# ROS-Robot-Controller.net
KiCad netlist of a schematic drawn in Altium Designer
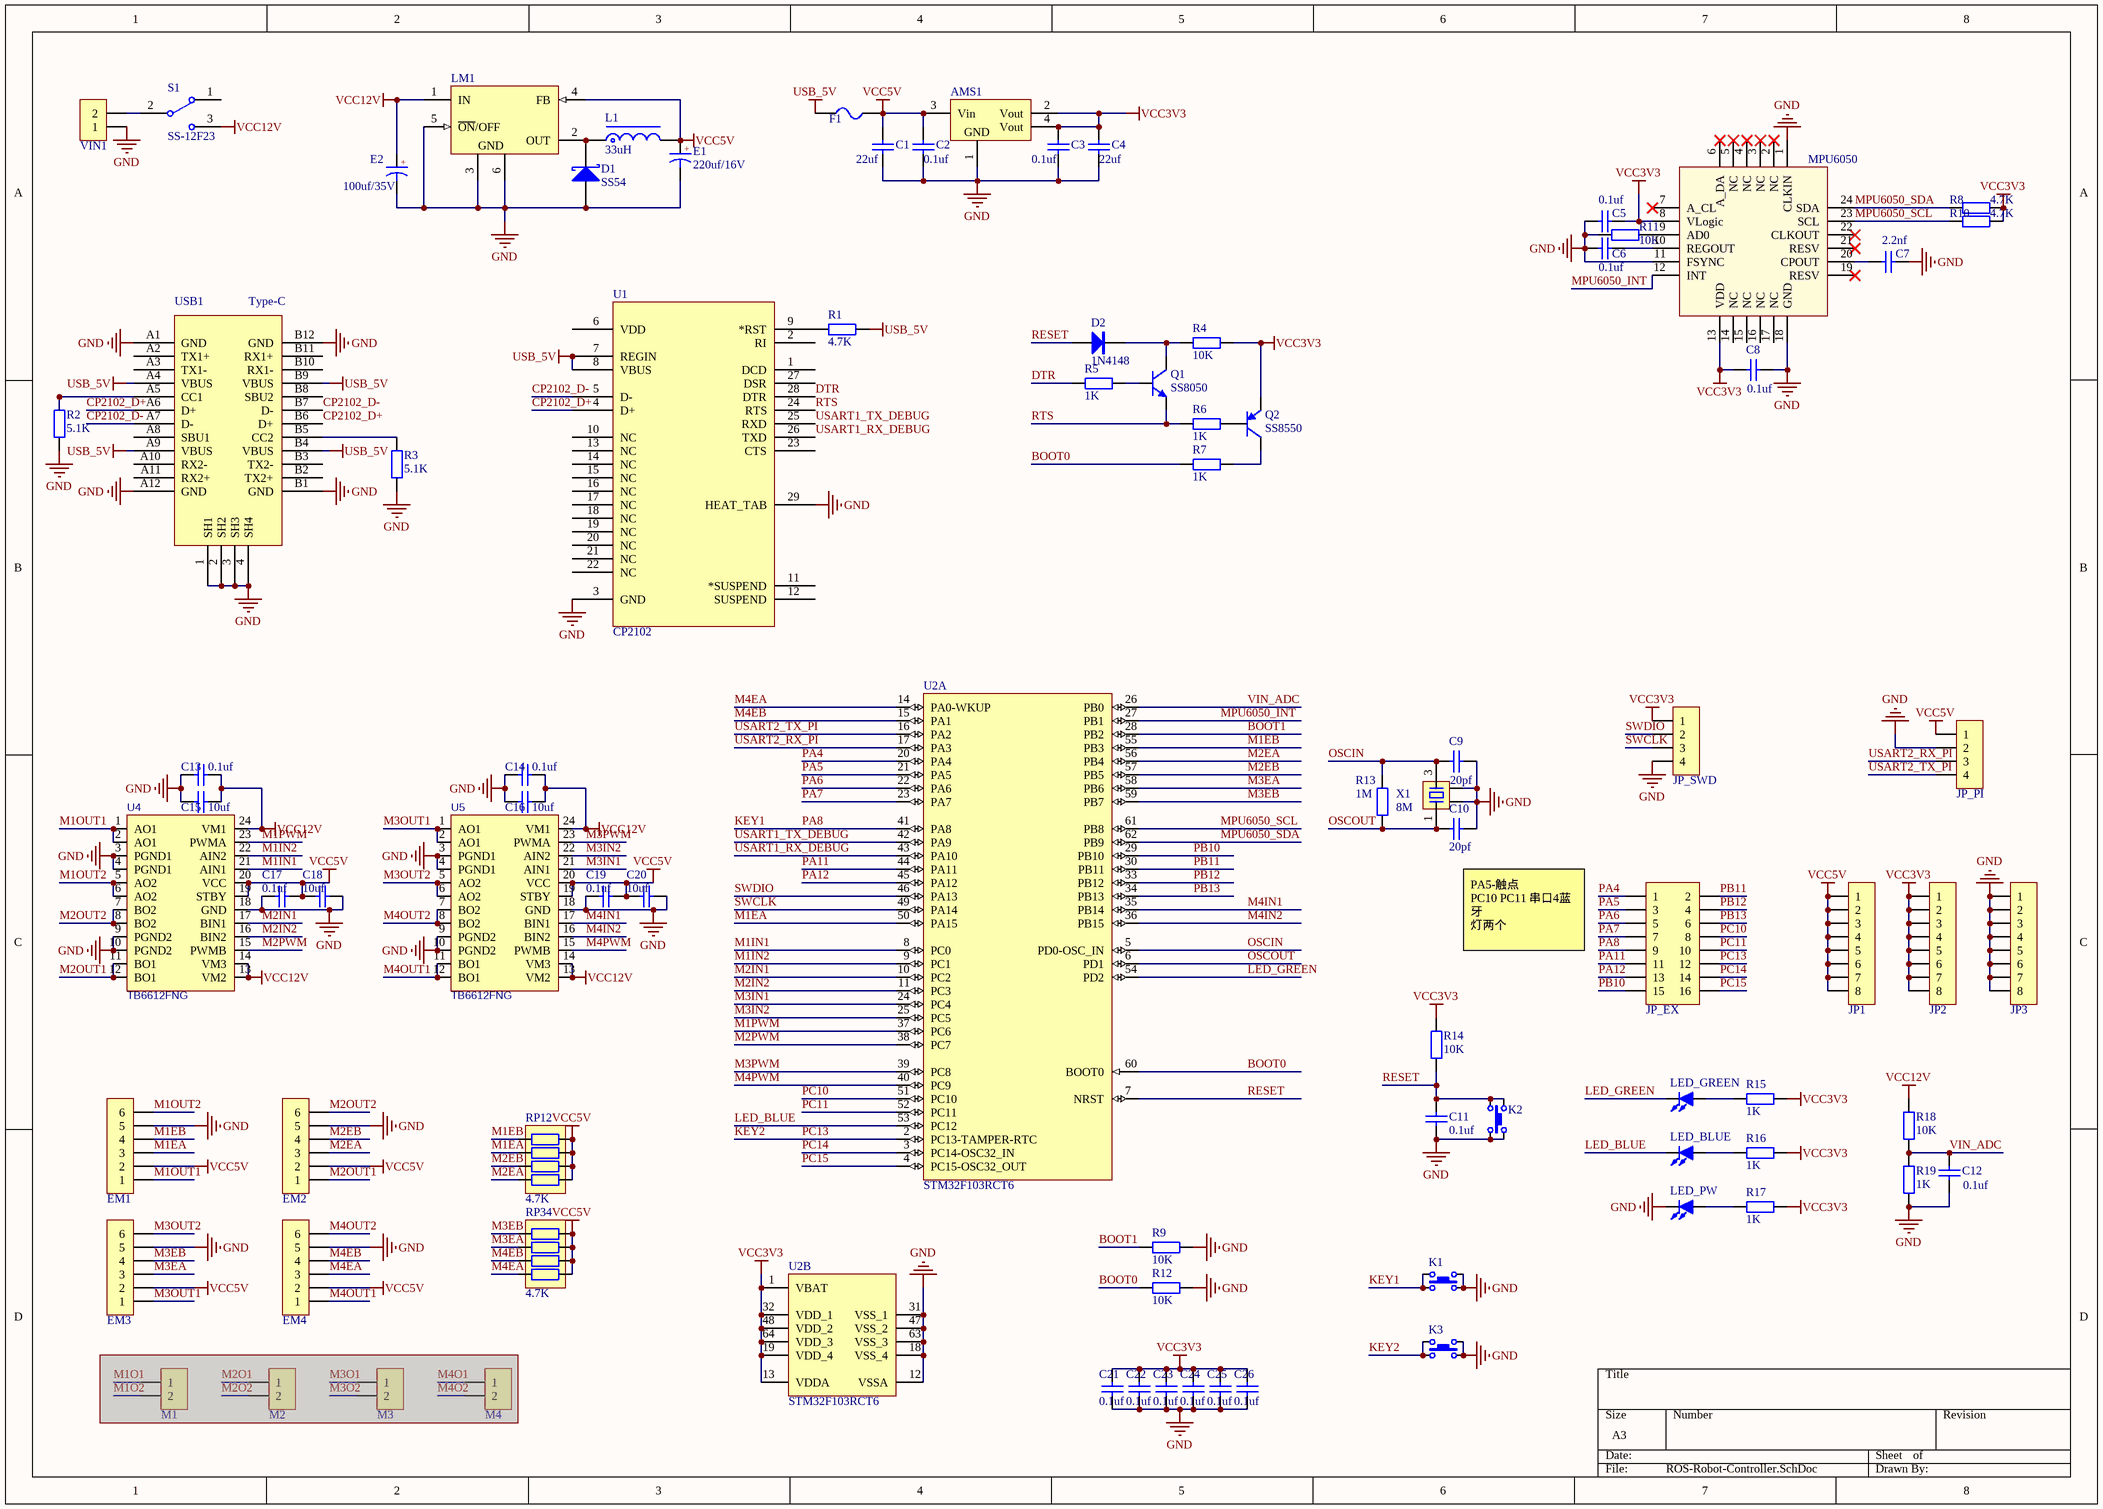
[diagram p0: ROS-Robot-Controller.SchDoc]

(export (version "E")
  (design (tool "Eeschema 10.0.6"))
  (components
    (comp (ref "AMS1")
      (value "AMS1117-3V3")
      (footprint "SOT223_L")
      (description "三端稳压芯片")
      (libsource (lib "1.1 - 电源类芯片") (part "AMS1117"))
    )
    (comp (ref "C1")
      (value "22uf")
      (footprint "C0402_L")
      (description "贴片电容")
      (libsource (lib "0.1 - 电阻-电容-电感-电位器") (part "C"))
    )
    (comp (ref "C2")
      (value "0.1uf")
      (footprint "C0402_L")
      (description "贴片电容")
      (libsource (lib "0.1 - 电阻-电容-电感-电位器") (part "C"))
    )
    (comp (ref "C3")
      (value "0.1uf")
      (footprint "C0402_L")
      (description "贴片电容")
      (libsource (lib "0.1 - 电阻-电容-电感-电位器") (part "C"))
    )
    (comp (ref "C4")
      (value "22uf")
      (footprint "C0402_L")
      (description "贴片电容")
      (libsource (lib "0.1 - 电阻-电容-电感-电位器") (part "C"))
    )
    (comp (ref "C5")
      (value "0.1uf")
      (footprint "C0402_L")
      (description "贴片电容")
      (libsource (lib "0.1 - 电阻-电容-电感-电位器") (part "C"))
    )
    (comp (ref "C6")
      (value "0.1uf")
      (footprint "C0402_L")
      (description "贴片电容")
      (libsource (lib "0.1 - 电阻-电容-电感-电位器") (part "C"))
    )
    (comp (ref "C7")
      (value "2.2nf")
      (footprint "C0402_L")
      (description "贴片电容")
      (libsource (lib "0.1 - 电阻-电容-电感-电位器") (part "C"))
    )
    (comp (ref "C8")
      (value "0.1uf")
      (footprint "C0402_L")
      (description "贴片电容")
      (libsource (lib "0.1 - 电阻-电容-电感-电位器") (part "C"))
    )
    (comp (ref "C9")
      (value "20pf")
      (footprint "C0402_L")
      (description "贴片电容")
      (libsource (lib "0.1 - 电阻-电容-电感-电位器") (part "C"))
    )
    (comp (ref "C10")
      (value "20pf")
      (footprint "C0402_L")
      (description "贴片电容")
      (libsource (lib "0.1 - 电阻-电容-电感-电位器") (part "C"))
    )
    (comp (ref "C11")
      (value "0.1uf")
      (footprint "C0402_L")
      (description "贴片电容")
      (libsource (lib "0.1 - 电阻-电容-电感-电位器") (part "C"))
    )
    (comp (ref "C12")
      (value "0.1uf")
      (footprint "C0603_L")
      (description "贴片电容")
      (libsource (lib "0.1 - 电阻-电容-电感-电位器") (part "C"))
    )
    (comp (ref "C13")
      (value "0.1uf")
      (footprint "C0603_L")
      (description "贴片电容")
      (libsource (lib "0.1 - 电阻-电容-电感-电位器") (part "C"))
    )
    (comp (ref "C14")
      (value "0.1uf")
      (footprint "C0603_L")
      (description "贴片电容")
      (libsource (lib "0.1 - 电阻-电容-电感-电位器") (part "C"))
    )
    (comp (ref "C15")
      (value "10uf")
      (footprint "C0603_L")
      (description "贴片电容")
      (libsource (lib "0.1 - 电阻-电容-电感-电位器") (part "C"))
    )
    (comp (ref "C16")
      (value "10uf")
      (footprint "C0603_L")
      (description "贴片电容")
      (libsource (lib "0.1 - 电阻-电容-电感-电位器") (part "C"))
    )
    (comp (ref "C17")
      (value "0.1uf")
      (footprint "C0402_L")
      (description "贴片电容")
      (libsource (lib "0.1 - 电阻-电容-电感-电位器") (part "C"))
    )
    (comp (ref "C18")
      (value "10uf")
      (footprint "C0402_L")
      (description "贴片电容")
      (libsource (lib "0.1 - 电阻-电容-电感-电位器") (part "C"))
    )
    (comp (ref "C19")
      (value "0.1uf")
      (footprint "C0402_L")
      (description "贴片电容")
      (libsource (lib "0.1 - 电阻-电容-电感-电位器") (part "C"))
    )
    (comp (ref "C20")
      (value "10uf")
      (footprint "C0402_L")
      (description "贴片电容")
      (libsource (lib "0.1 - 电阻-电容-电感-电位器") (part "C"))
    )
    (comp (ref "C21")
      (value "0.1uf")
      (footprint "C0402_L")
      (description "贴片电容")
      (libsource (lib "0.1 - 电阻-电容-电感-电位器") (part "C"))
    )
    (comp (ref "C22")
      (value "0.1uf")
      (footprint "C0402_L")
      (description "贴片电容")
      (libsource (lib "0.1 - 电阻-电容-电感-电位器") (part "C"))
    )
    (comp (ref "C23")
      (value "0.1uf")
      (footprint "C0402_L")
      (description "贴片电容")
      (libsource (lib "0.1 - 电阻-电容-电感-电位器") (part "C"))
    )
    (comp (ref "C24")
      (value "0.1uf")
      (footprint "C0402_L")
      (description "贴片电容")
      (libsource (lib "0.1 - 电阻-电容-电感-电位器") (part "C"))
    )
    (comp (ref "C25")
      (value "0.1uf")
      (footprint "C0402_L")
      (description "贴片电容")
      (libsource (lib "0.1 - 电阻-电容-电感-电位器") (part "C"))
    )
    (comp (ref "C26")
      (value "0.1uf")
      (footprint "C0402_L")
      (description "贴片电容")
      (libsource (lib "0.1 - 电阻-电容-电感-电位器") (part "C"))
    )
    (comp (ref "D1")
      (value "SS54")
      (footprint "SMA")
      (description "肖特基二极管(5A/40V)")
      (libsource (lib "0.2 - 二极管-TVS-整流桥") (part "SS14"))
    )
    (comp (ref "D2")
      (value "1N4148")
      (footprint "SOD-323")
      (description "开关二极管")
      (libsource (lib "0.2 - 二极管-TVS-整流桥") (part "1N4148"))
    )
    (comp (ref "E1")
      (value "220uf/16V")
      (footprint "CE D(6.3*7.7)")
      (description "贴片电解电容")
      (libsource (lib "0.1 - 电阻-电容-电感-电位器") (part "CE_SMD"))
    )
    (comp (ref "E2")
      (value "100uf/35V")
      (footprint "CE D(6.3*7.7)")
      (description "贴片电解电容")
      (libsource (lib "0.1 - 电阻-电容-电感-电位器") (part "CE_SMD"))
    )
    (comp (ref "EM1")
      (value "HDR-1X6")
      (footprint "XH2.54-LI-6P")
      (description "6P接插件")
      (libsource (lib "5.4 - 接插件-脚距2.54 (100mil) ") (part "Header 6"))
    )
    (comp (ref "EM2")
      (value "HDR-1X6")
      (footprint "XH2.54-LI-6P")
      (description "6P接插件")
      (libsource (lib "5.4 - 接插件-脚距2.54 (100mil) ") (part "Header 6"))
    )
    (comp (ref "EM3")
      (value "HDR-1X6")
      (footprint "XH2.54-LI-6P")
      (description "6P接插件")
      (libsource (lib "5.4 - 接插件-脚距2.54 (100mil) ") (part "Header 6"))
    )
    (comp (ref "EM4")
      (value "HDR-1X6")
      (footprint "XH2.54-LI-6P")
      (description "6P接插件")
      (libsource (lib "5.4 - 接插件-脚距2.54 (100mil) ") (part "Header 6"))
    )
    (comp (ref "F1")
      (value "MSMD200-8V 2A")
      (footprint "FU 0603")
      (description "贴片保险丝")
      (libsource (lib "0.5 - 保险丝-晶振-光耦") (part "FU"))
    )
    (comp (ref "JP1")
      (value "HDR-1X8")
      (footprint "HDR2.54-LI-8P")
      (description "8P接插件")
      (libsource (lib "5.4 - 接插件-脚距2.54 (100mil) ") (part "Header 8"))
    )
    (comp (ref "JP2")
      (value "HDR-1X8")
      (footprint "HDR2.54-LI-8P")
      (description "8P接插件")
      (libsource (lib "5.4 - 接插件-脚距2.54 (100mil) ") (part "Header 8"))
    )
    (comp (ref "JP3")
      (value "HDR-1X8")
      (footprint "HDR2.54-LI-8P")
      (description "8P接插件")
      (libsource (lib "5.4 - 接插件-脚距2.54 (100mil) ") (part "Header 8"))
    )
    (comp (ref "JP_EX")
      (value "Header 8X2")
      (footprint "HDR2.54-LI-2x8P")
      (description "8*2P接插件")
      (libsource (lib "5.4 - 接插件-脚距2.54 (100mil) ") (part "Header 8X2"))
    )
    (comp (ref "JP_PI")
      (value "HDR-1X4")
      (footprint "HDR2.54-LI-4P")
      (description "4P接插件")
      (libsource (lib "5.4 - 接插件-脚距2.54 (100mil) ") (part "Header 4"))
    )
    (comp (ref "JP_SWD")
      (value "HDR-1X4")
      (footprint "XH2.54-WI-4P")
      (description "4P接插件")
      (libsource (lib "5.4 - 接插件-脚距2.54 (100mil) ") (part "Header 4"))
    )
    (comp (ref "K1")
      (value "TACT 4P")
      (footprint "SW-SMD_4P-L4.2-W3.3-P2.15-LS5.1")
      (description "Button")
      (libsource (lib "KitSprout") (part "ButtonTACT"))
    )
    (comp (ref "K2")
      (value "TACT 4P")
      (footprint "SW-SMD_4P-L4.2-W3.3-P2.15-LS5.1")
      (description "Button")
      (libsource (lib "KitSprout") (part "ButtonTACT"))
    )
    (comp (ref "K3")
      (value "TACT 4P")
      (footprint "SW-SMD_4P-L4.2-W3.3-P2.15-LS5.1")
      (description "Button")
      (libsource (lib "KitSprout") (part "ButtonTACT"))
    )
    (comp (ref "L1")
      (value "33uH")
      (footprint "CDRH74")
      (description "CDRH功率屏蔽电感")
      (libsource (lib "0.1 - 电阻-电容-电感-电位器") (part "L-CDRH"))
    )
    (comp (ref "LED_BLUE")
      (value "红色")
      (footprint "LED_0402_RED")
      (description "贴片LED")
      (libsource (lib "0.3 - LED发光二极管") (part "LED-SMD"))
    )
    (comp (ref "LED_GREEN")
      (value "红色")
      (footprint "LED_0402_RED")
      (description "贴片LED")
      (libsource (lib "0.3 - LED发光二极管") (part "LED-SMD"))
    )
    (comp (ref "LED_PW")
      (value "红色")
      (footprint "LED_0402_RED")
      (description "贴片LED")
      (libsource (lib "0.3 - LED发光二极管") (part "LED-SMD"))
    )
    (comp (ref "LM1")
      (value "LM2596S")
      (footprint "TO263-5A")
      (description "3A DC-DC降压芯片")
      (libsource (lib "1.1 - 电源类芯片") (part "LM2596S"))
    )
    (comp (ref "M1")
      (value "HDR-1X2")
      (footprint "KF350-2P")
      (description "2P接插件")
      (libsource (lib "5.5 - 接插件-脚距3.5") (part "Header 2"))
    )
    (comp (ref "M2")
      (value "HDR-1X2")
      (footprint "KF350-2P")
      (description "2P接插件")
      (libsource (lib "5.5 - 接插件-脚距3.5") (part "Header 2"))
    )
    (comp (ref "M3")
      (value "HDR-1X2")
      (footprint "KF350-2P")
      (description "2P接插件")
      (libsource (lib "5.5 - 接插件-脚距3.5") (part "Header 2"))
    )
    (comp (ref "M4")
      (value "HDR-1X2")
      (footprint "KF350-2P")
      (description "2P接插件")
      (libsource (lib "5.5 - 接插件-脚距3.5") (part "Header 2"))
    )
    (comp (ref "Q1")
      (value "SS8050")
      (footprint "SOT23-3N")
      (description "高频放大-NPN型")
      (libsource (lib "0.4 - 三极管-场效应管-可控硅") (part "8050-SMD"))
    )
    (comp (ref "Q2")
      (value "SS8550")
      (footprint "SOT23-3N")
      (description "高频放大-PNP型")
      (libsource (lib "0.4 - 三极管-场效应管-可控硅") (part "8550-SMD"))
    )
    (comp (ref "R1")
      (value "4.7K")
      (footprint "R0402_L")
      (description "贴片电阻")
      (libsource (lib "0.1 - 电阻-电容-电感-电位器") (part "R"))
    )
    (comp (ref "R2")
      (value "5.1K")
      (footprint "R0402_L")
      (description "贴片电阻")
      (libsource (lib "0.1 - 电阻-电容-电感-电位器") (part "R"))
    )
    (comp (ref "R3")
      (value "5.1K")
      (footprint "R0402_L")
      (description "贴片电阻")
      (libsource (lib "0.1 - 电阻-电容-电感-电位器") (part "R"))
    )
    (comp (ref "R4")
      (value "10K")
      (footprint "R0402_L")
      (description "贴片电阻")
      (libsource (lib "0.1 - 电阻-电容-电感-电位器") (part "R"))
    )
    (comp (ref "R5")
      (value "1K")
      (footprint "R0402_L")
      (description "贴片电阻")
      (libsource (lib "0.1 - 电阻-电容-电感-电位器") (part "R"))
    )
    (comp (ref "R6")
      (value "1K")
      (footprint "R0402_L")
      (description "贴片电阻")
      (libsource (lib "0.1 - 电阻-电容-电感-电位器") (part "R"))
    )
    (comp (ref "R7")
      (value "1K")
      (footprint "R0402_L")
      (description "贴片电阻")
      (libsource (lib "0.1 - 电阻-电容-电感-电位器") (part "R"))
    )
    (comp (ref "R8")
      (value "4.7K")
      (footprint "R0402_L")
      (description "贴片电阻")
      (libsource (lib "0.1 - 电阻-电容-电感-电位器") (part "R"))
    )
    (comp (ref "R9")
      (value "10K")
      (footprint "R0402_L")
      (description "贴片电阻")
      (libsource (lib "0.1 - 电阻-电容-电感-电位器") (part "R"))
    )
    (comp (ref "R10")
      (value "4.7K")
      (footprint "R0402_L")
      (description "贴片电阻")
      (libsource (lib "0.1 - 电阻-电容-电感-电位器") (part "R"))
    )
    (comp (ref "R11")
      (value "10K")
      (footprint "R0402_L")
      (description "贴片电阻")
      (libsource (lib "0.1 - 电阻-电容-电感-电位器") (part "R"))
    )
    (comp (ref "R12")
      (value "10K")
      (footprint "R0402_L")
      (description "贴片电阻")
      (libsource (lib "0.1 - 电阻-电容-电感-电位器") (part "R"))
    )
    (comp (ref "R13")
      (value "1M")
      (footprint "R0402_L")
      (description "贴片电阻")
      (libsource (lib "0.1 - 电阻-电容-电感-电位器") (part "R"))
    )
    (comp (ref "R14")
      (value "10K")
      (footprint "R0402_L")
      (description "贴片电阻")
      (libsource (lib "0.1 - 电阻-电容-电感-电位器") (part "R"))
    )
    (comp (ref "R15")
      (value "1K")
      (footprint "R0402_L")
      (description "贴片电阻")
      (libsource (lib "0.1 - 电阻-电容-电感-电位器") (part "R"))
    )
    (comp (ref "R16")
      (value "1K")
      (footprint "R0402_L")
      (description "贴片电阻")
      (libsource (lib "0.1 - 电阻-电容-电感-电位器") (part "R"))
    )
    (comp (ref "R17")
      (value "1K")
      (footprint "R0402_L")
      (description "贴片电阻")
      (libsource (lib "0.1 - 电阻-电容-电感-电位器") (part "R"))
    )
    (comp (ref "R18")
      (value "10K")
      (footprint "R0603_L")
      (description "贴片电阻")
      (libsource (lib "0.1 - 电阻-电容-电感-电位器") (part "R"))
    )
    (comp (ref "R19")
      (value "1K")
      (footprint "R0603_L")
      (description "贴片电阻")
      (libsource (lib "0.1 - 电阻-电容-电感-电位器") (part "R"))
    )
    (comp (ref "RP12")
      (value "4.7K")
      (footprint "RCA-8P4R-0402")
      (description "贴片4P排阻")
      (libsource (lib "0.1 - 电阻-电容-电感-电位器") (part "R-8P4R"))
    )
    (comp (ref "RP34")
      (value "4.7K")
      (footprint "RCA-8P4R-0402")
      (description "贴片4P排阻")
      (libsource (lib "0.1 - 电阻-电容-电感-电位器") (part "R-8P4R"))
    )
    (comp (ref "S1")
      (value "SS-12F23")
      (footprint "SS-12D10")
      (description "1路波动开关")
      (libsource (lib "0.7 - 常用按键-开关-蜂鸣器-电池-测试点") (part "SSW-1P"))
    )
    (comp (ref "U1")
      (value "CP2102")
      (footprint "QFN-28")
      (description "USB转TTL")
      (libsource (lib "mLib") (part "CP2102"))
    )
    (comp (ref "U2")
      (value "STM32F103RCT6")
      (footprint "LQFP64_N")
      (libsource (lib "2.4 - STM32 F1系列单片机") (part "STM32F103RCT6"))
    )
    (comp (ref "U3")
      (value "MPU6050")
      (footprint "QFN-24")
      (description "六轴传感器")
      (libsource (lib "mLib") (part "MPU6050"))
    )
    (comp (ref "U4")
      (value "TB6612FNG")
      (footprint "SSOP24_M")
      (description "电机驱动")
      (libsource (lib "1.0 - 常见芯片") (part "TB6612FNG"))
    )
    (comp (ref "U5")
      (value "TB6612FNG")
      (footprint "SSOP24_M")
      (description "电机驱动")
      (libsource (lib "1.0 - 常见芯片") (part "TB6612FNG"))
    )
    (comp (ref "USB1")
      (value "Type-C")
      (footprint "Type-C-TOP")
      (libsource (lib "MyPcbLib") (part "USB-Type-C-TOP"))
    )
    (comp (ref "VIN1")
      (value "HDR-1X2")
      (footprint "KF301-5.0-2P")
      (description "2P接插件")
      (libsource (lib "6.0 - 接插件-脚距5.0") (part "Header 2"))
    )
    (comp (ref "X1")
      (value "8M")
      (footprint "OSC 3225-4P")
      (description "4脚无源晶振")
      (libsource (lib "0.5 - 保险丝-晶振-光耦") (part "XTAL-4P"))
    )
  )
  (nets
    (net (code "1") (name "/BOOT0") (class "Default")
      (node (ref "R12") (pin "1") (pinfunction "1_1") (pintype "passive"))
      (node (ref "R7") (pin "2") (pinfunction "2_2") (pintype "passive"))
      (node (ref "U2") (pin "60") (pinfunction "BOOT0_60") (pintype "input"))
    )
    (net (code "2") (name "/BOOT1") (class "Default")
      (node (ref "R9") (pin "1") (pinfunction "1_1") (pintype "passive"))
      (node (ref "U2") (pin "28") (pinfunction "PB2_28") (pintype "bidirectional"))
    )
    (net (code "3") (name "/CP2102_D+") (class "Default")
      (node (ref "U1") (pin "4") (pinfunction "D+_4") (pintype "passive"))
      (node (ref "USB1") (pin "A6") (pinfunction "D+_A6") (pintype "passive"))
      (node (ref "USB1") (pin "B6") (pinfunction "D+_B6") (pintype "passive"))
    )
    (net (code "4") (name "/CP2102_D-") (class "Default")
      (node (ref "U1") (pin "5") (pinfunction "D-_5") (pintype "passive"))
      (node (ref "USB1") (pin "A7") (pinfunction "D-_A7") (pintype "passive"))
      (node (ref "USB1") (pin "B7") (pinfunction "D-_B7") (pintype "passive"))
    )
    (net (code "5") (name "/DTR") (class "Default")
      (node (ref "R5") (pin "1") (pinfunction "1_1") (pintype "passive"))
      (node (ref "U1") (pin "28") (pinfunction "DTR_28") (pintype "passive"))
    )
    (net (code "6") (name "/KEY1") (class "Default")
      (node (ref "JP_EX") (pin "9") (pinfunction "9_9") (pintype "passive"))
      (node (ref "K1") (pin "1") (pinfunction "1_1") (pintype "passive"))
      (node (ref "K1") (pin "3") (pinfunction "3_3") (pintype "passive"))
      (node (ref "U2") (pin "41") (pinfunction "PA8_41") (pintype "bidirectional"))
    )
    (net (code "7") (name "/KEY2") (class "Default")
      (node (ref "JP_EX") (pin "12") (pinfunction "12_12") (pintype "passive"))
      (node (ref "K3") (pin "1") (pinfunction "1_1") (pintype "passive"))
      (node (ref "K3") (pin "3") (pinfunction "3_3") (pintype "passive"))
      (node (ref "U2") (pin "2") (pinfunction "PC13-TAMPER-RTC_2") (pintype "bidirectional"))
    )
    (net (code "8") (name "/LED_BLUE") (class "Default")
      (node (ref "LED_BLUE") (pin "2") (pinfunction "K_2") (pintype "passive"))
      (node (ref "U2") (pin "53") (pinfunction "PC12_53") (pintype "bidirectional"))
    )
    (net (code "9") (name "/LED_GREEN") (class "Default")
      (node (ref "LED_GREEN") (pin "2") (pinfunction "K_2") (pintype "passive"))
      (node (ref "U2") (pin "54") (pinfunction "PD2_54") (pintype "bidirectional"))
    )
    (net (code "10") (name "/M1EA") (class "Default")
      (node (ref "EM1") (pin "3") (pinfunction "3_3") (pintype "passive"))
      (node (ref "RP12") (pin "2") (pinfunction "2_2") (pintype "passive"))
      (node (ref "U2") (pin "50") (pinfunction "PA15_50") (pintype "bidirectional"))
    )
    (net (code "11") (name "/M1EB") (class "Default")
      (node (ref "EM1") (pin "4") (pinfunction "4_4") (pintype "passive"))
      (node (ref "RP12") (pin "1") (pinfunction "1_1") (pintype "passive"))
      (node (ref "U2") (pin "55") (pinfunction "PB3_55") (pintype "bidirectional"))
    )
    (net (code "12") (name "/M1IN1") (class "Default")
      (node (ref "U2") (pin "8") (pinfunction "PC0_8") (pintype "bidirectional"))
      (node (ref "U4") (pin "21") (pinfunction "AIN1_21") (pintype "passive"))
    )
    (net (code "13") (name "/M1IN2") (class "Default")
      (node (ref "U2") (pin "9") (pinfunction "PC1_9") (pintype "bidirectional"))
      (node (ref "U4") (pin "22") (pinfunction "AIN2_22") (pintype "passive"))
    )
    (net (code "14") (name "/M1O1") (class "Default")
      (node (ref "M1") (pin "1") (pinfunction "1_1") (pintype "passive"))
    )
    (net (code "15") (name "/M1O2") (class "Default")
      (node (ref "M1") (pin "2") (pinfunction "2_2") (pintype "passive"))
    )
    (net (code "16") (name "/M1OUT1") (class "Default")
      (node (ref "EM1") (pin "1") (pinfunction "1_1") (pintype "passive"))
      (node (ref "U4") (pin "1") (pinfunction "AO1_1") (pintype "passive"))
      (node (ref "U4") (pin "2") (pinfunction "AO1_2") (pintype "passive"))
    )
    (net (code "17") (name "/M1OUT2") (class "Default")
      (node (ref "EM1") (pin "6") (pinfunction "6_6") (pintype "passive"))
      (node (ref "U4") (pin "5") (pinfunction "AO2_5") (pintype "passive"))
      (node (ref "U4") (pin "6") (pinfunction "AO2_6") (pintype "passive"))
    )
    (net (code "18") (name "/M1PWM") (class "Default")
      (node (ref "U2") (pin "37") (pinfunction "PC6_37") (pintype "bidirectional"))
      (node (ref "U4") (pin "23") (pinfunction "PWMA_23") (pintype "passive"))
    )
    (net (code "19") (name "/M2EA") (class "Default")
      (node (ref "EM2") (pin "3") (pinfunction "3_3") (pintype "passive"))
      (node (ref "RP12") (pin "4") (pinfunction "4_4") (pintype "passive"))
      (node (ref "U2") (pin "56") (pinfunction "PB4_56") (pintype "bidirectional"))
    )
    (net (code "20") (name "/M2EB") (class "Default")
      (node (ref "EM2") (pin "4") (pinfunction "4_4") (pintype "passive"))
      (node (ref "RP12") (pin "3") (pinfunction "3_3") (pintype "passive"))
      (node (ref "U2") (pin "57") (pinfunction "PB5_57") (pintype "bidirectional"))
    )
    (net (code "21") (name "/M2IN1") (class "Default")
      (node (ref "U2") (pin "10") (pinfunction "PC2_10") (pintype "bidirectional"))
      (node (ref "U4") (pin "17") (pinfunction "BIN1_17") (pintype "passive"))
    )
    (net (code "22") (name "/M2IN2") (class "Default")
      (node (ref "U2") (pin "11") (pinfunction "PC3_11") (pintype "bidirectional"))
      (node (ref "U4") (pin "16") (pinfunction "BIN2_16") (pintype "passive"))
    )
    (net (code "23") (name "/M2O1") (class "Default")
      (node (ref "M2") (pin "1") (pinfunction "1_1") (pintype "passive"))
    )
    (net (code "24") (name "/M2O2") (class "Default")
      (node (ref "M2") (pin "2") (pinfunction "2_2") (pintype "passive"))
    )
    (net (code "25") (name "/M2OUT1") (class "Default")
      (node (ref "EM2") (pin "1") (pinfunction "1_1") (pintype "passive"))
      (node (ref "U4") (pin "11") (pinfunction "BO1_11") (pintype "passive"))
      (node (ref "U4") (pin "12") (pinfunction "BO1_12") (pintype "passive"))
    )
    (net (code "26") (name "/M2OUT2") (class "Default")
      (node (ref "EM2") (pin "6") (pinfunction "6_6") (pintype "passive"))
      (node (ref "U4") (pin "7") (pinfunction "BO2_7") (pintype "passive"))
      (node (ref "U4") (pin "8") (pinfunction "BO2_8") (pintype "passive"))
    )
    (net (code "27") (name "/M2PWM") (class "Default")
      (node (ref "U2") (pin "38") (pinfunction "PC7_38") (pintype "bidirectional"))
      (node (ref "U4") (pin "15") (pinfunction "PWMB_15") (pintype "passive"))
    )
    (net (code "28") (name "/M3EA") (class "Default")
      (node (ref "EM3") (pin "3") (pinfunction "3_3") (pintype "passive"))
      (node (ref "RP34") (pin "2") (pinfunction "2_2") (pintype "passive"))
      (node (ref "U2") (pin "58") (pinfunction "PB6_58") (pintype "bidirectional"))
    )
    (net (code "29") (name "/M3EB") (class "Default")
      (node (ref "EM3") (pin "4") (pinfunction "4_4") (pintype "passive"))
      (node (ref "RP34") (pin "1") (pinfunction "1_1") (pintype "passive"))
      (node (ref "U2") (pin "59") (pinfunction "PB7_59") (pintype "bidirectional"))
    )
    (net (code "30") (name "/M3IN1") (class "Default")
      (node (ref "U2") (pin "24") (pinfunction "PC4_24") (pintype "bidirectional"))
      (node (ref "U5") (pin "21") (pinfunction "AIN1_21") (pintype "passive"))
    )
    (net (code "31") (name "/M3IN2") (class "Default")
      (node (ref "U2") (pin "25") (pinfunction "PC5_25") (pintype "bidirectional"))
      (node (ref "U5") (pin "22") (pinfunction "AIN2_22") (pintype "passive"))
    )
    (net (code "32") (name "/M3O1") (class "Default")
      (node (ref "M3") (pin "1") (pinfunction "1_1") (pintype "passive"))
    )
    (net (code "33") (name "/M3O2") (class "Default")
      (node (ref "M3") (pin "2") (pinfunction "2_2") (pintype "passive"))
    )
    (net (code "34") (name "/M3OUT1") (class "Default")
      (node (ref "EM3") (pin "1") (pinfunction "1_1") (pintype "passive"))
      (node (ref "U5") (pin "1") (pinfunction "AO1_1") (pintype "passive"))
      (node (ref "U5") (pin "2") (pinfunction "AO1_2") (pintype "passive"))
    )
    (net (code "35") (name "/M3OUT2") (class "Default")
      (node (ref "EM3") (pin "6") (pinfunction "6_6") (pintype "passive"))
      (node (ref "U5") (pin "5") (pinfunction "AO2_5") (pintype "passive"))
      (node (ref "U5") (pin "6") (pinfunction "AO2_6") (pintype "passive"))
    )
    (net (code "36") (name "/M3PWM") (class "Default")
      (node (ref "U2") (pin "39") (pinfunction "PC8_39") (pintype "bidirectional"))
      (node (ref "U5") (pin "23") (pinfunction "PWMA_23") (pintype "passive"))
    )
    (net (code "37") (name "/M4EA") (class "Default")
      (node (ref "EM4") (pin "3") (pinfunction "3_3") (pintype "passive"))
      (node (ref "RP34") (pin "4") (pinfunction "4_4") (pintype "passive"))
      (node (ref "U2") (pin "14") (pinfunction "PA0-WKUP_14") (pintype "bidirectional"))
    )
    (net (code "38") (name "/M4EB") (class "Default")
      (node (ref "EM4") (pin "4") (pinfunction "4_4") (pintype "passive"))
      (node (ref "RP34") (pin "3") (pinfunction "3_3") (pintype "passive"))
      (node (ref "U2") (pin "15") (pinfunction "PA1_15") (pintype "bidirectional"))
    )
    (net (code "39") (name "/M4IN1") (class "Default")
      (node (ref "U2") (pin "35") (pinfunction "PB14_35") (pintype "bidirectional"))
      (node (ref "U5") (pin "17") (pinfunction "BIN1_17") (pintype "passive"))
    )
    (net (code "40") (name "/M4IN2") (class "Default")
      (node (ref "U2") (pin "36") (pinfunction "PB15_36") (pintype "bidirectional"))
      (node (ref "U5") (pin "16") (pinfunction "BIN2_16") (pintype "passive"))
    )
    (net (code "41") (name "/M4O1") (class "Default")
      (node (ref "M4") (pin "1") (pinfunction "1_1") (pintype "passive"))
    )
    (net (code "42") (name "/M4O2") (class "Default")
      (node (ref "M4") (pin "2") (pinfunction "2_2") (pintype "passive"))
    )
    (net (code "43") (name "/M4OUT1") (class "Default")
      (node (ref "EM4") (pin "1") (pinfunction "1_1") (pintype "passive"))
      (node (ref "U5") (pin "11") (pinfunction "BO1_11") (pintype "passive"))
      (node (ref "U5") (pin "12") (pinfunction "BO1_12") (pintype "passive"))
    )
    (net (code "44") (name "/M4OUT2") (class "Default")
      (node (ref "EM4") (pin "6") (pinfunction "6_6") (pintype "passive"))
      (node (ref "U5") (pin "7") (pinfunction "BO2_7") (pintype "passive"))
      (node (ref "U5") (pin "8") (pinfunction "BO2_8") (pintype "passive"))
    )
    (net (code "45") (name "/M4PWM") (class "Default")
      (node (ref "U2") (pin "40") (pinfunction "PC9_40") (pintype "bidirectional"))
      (node (ref "U5") (pin "15") (pinfunction "PWMB_15") (pintype "passive"))
    )
    (net (code "46") (name "/MPU6050_INT") (class "Default")
      (node (ref "U2") (pin "27") (pinfunction "PB1_27") (pintype "bidirectional"))
      (node (ref "U3") (pin "12") (pinfunction "INT_12") (pintype "passive"))
    )
    (net (code "47") (name "/MPU6050_SCL") (class "Default")
      (node (ref "R10") (pin "1") (pinfunction "1_1") (pintype "passive"))
      (node (ref "U2") (pin "61") (pinfunction "PB8_61") (pintype "bidirectional"))
      (node (ref "U3") (pin "23") (pinfunction "SCL_23") (pintype "passive"))
    )
    (net (code "48") (name "/MPU6050_SDA") (class "Default")
      (node (ref "R8") (pin "1") (pinfunction "1_1") (pintype "passive"))
      (node (ref "U2") (pin "62") (pinfunction "PB9_62") (pintype "bidirectional"))
      (node (ref "U3") (pin "24") (pinfunction "SDA_24") (pintype "passive"))
    )
    (net (code "49") (name "/OSCIN") (class "Default")
      (node (ref "C9") (pin "1") (pinfunction "1_1") (pintype "passive"))
      (node (ref "R13") (pin "2") (pinfunction "2_2") (pintype "passive"))
      (node (ref "U2") (pin "5") (pinfunction "PD0-OSC_IN_5") (pintype "bidirectional"))
      (node (ref "X1") (pin "3") (pinfunction "3_3") (pintype "passive"))
    )
    (net (code "50") (name "/OSCOUT") (class "Default")
      (node (ref "C10") (pin "1") (pinfunction "1_1") (pintype "passive"))
      (node (ref "R13") (pin "1") (pinfunction "1_1") (pintype "passive"))
      (node (ref "U2") (pin "6") (pinfunction "PD1_6") (pintype "bidirectional"))
      (node (ref "X1") (pin "1") (pinfunction "1_1") (pintype "passive"))
    )
    (net (code "51") (name "/PA4") (class "Default")
      (node (ref "JP_EX") (pin "1") (pinfunction "1_1") (pintype "passive"))
      (node (ref "U2") (pin "20") (pinfunction "PA4_20") (pintype "bidirectional"))
    )
    (net (code "52") (name "/PA5") (class "Default")
      (node (ref "JP_EX") (pin "3") (pinfunction "3_3") (pintype "passive"))
      (node (ref "U2") (pin "21") (pinfunction "PA5_21") (pintype "bidirectional"))
    )
    (net (code "53") (name "/PA6") (class "Default")
      (node (ref "JP_EX") (pin "5") (pinfunction "5_5") (pintype "passive"))
      (node (ref "U2") (pin "22") (pinfunction "PA6_22") (pintype "bidirectional"))
    )
    (net (code "54") (name "/PA7") (class "Default")
      (node (ref "JP_EX") (pin "7") (pinfunction "7_7") (pintype "passive"))
      (node (ref "U2") (pin "23") (pinfunction "PA7_23") (pintype "bidirectional"))
    )
    (net (code "55") (name "/PA11") (class "Default")
      (node (ref "JP_EX") (pin "11") (pinfunction "11_11") (pintype "passive"))
      (node (ref "U2") (pin "44") (pinfunction "PA11_44") (pintype "bidirectional"))
    )
    (net (code "56") (name "/PA12") (class "Default")
      (node (ref "JP_EX") (pin "13") (pinfunction "13_13") (pintype "passive"))
      (node (ref "U2") (pin "45") (pinfunction "PA12_45") (pintype "bidirectional"))
    )
    (net (code "57") (name "/PB10") (class "Default")
      (node (ref "JP_EX") (pin "15") (pinfunction "15_15") (pintype "passive"))
      (node (ref "U2") (pin "29") (pinfunction "PB10_29") (pintype "bidirectional"))
    )
    (net (code "58") (name "/PB11") (class "Default")
      (node (ref "JP_EX") (pin "2") (pinfunction "2_2") (pintype "passive"))
      (node (ref "U2") (pin "30") (pinfunction "PB11_30") (pintype "bidirectional"))
    )
    (net (code "59") (name "/PB12") (class "Default")
      (node (ref "JP_EX") (pin "4") (pinfunction "4_4") (pintype "passive"))
      (node (ref "U2") (pin "33") (pinfunction "PB12_33") (pintype "bidirectional"))
    )
    (net (code "60") (name "/PB13") (class "Default")
      (node (ref "JP_EX") (pin "6") (pinfunction "6_6") (pintype "passive"))
      (node (ref "U2") (pin "34") (pinfunction "PB13_34") (pintype "bidirectional"))
    )
    (net (code "61") (name "/PC10") (class "Default")
      (node (ref "JP_EX") (pin "8") (pinfunction "8_8") (pintype "passive"))
      (node (ref "U2") (pin "51") (pinfunction "PC10_51") (pintype "bidirectional"))
    )
    (net (code "62") (name "/PC11") (class "Default")
      (node (ref "JP_EX") (pin "10") (pinfunction "10_10") (pintype "passive"))
      (node (ref "U2") (pin "52") (pinfunction "PC11_52") (pintype "bidirectional"))
    )
    (net (code "63") (name "/PC14") (class "Default")
      (node (ref "JP_EX") (pin "14") (pinfunction "14_14") (pintype "passive"))
      (node (ref "U2") (pin "3") (pinfunction "PC14-OSC32_IN_3") (pintype "bidirectional"))
    )
    (net (code "64") (name "/PC15") (class "Default")
      (node (ref "JP_EX") (pin "16") (pinfunction "16_16") (pintype "passive"))
      (node (ref "U2") (pin "4") (pinfunction "PC15-OSC32_OUT_4") (pintype "bidirectional"))
    )
    (net (code "65") (name "/RESET") (class "Default")
      (node (ref "C11") (pin "2") (pinfunction "2_2") (pintype "passive"))
      (node (ref "D2") (pin "1") (pinfunction "A_1") (pintype "passive"))
      (node (ref "K2") (pin "1") (pinfunction "1_1") (pintype "passive"))
      (node (ref "K2") (pin "3") (pinfunction "3_3") (pintype "passive"))
      (node (ref "R14") (pin "1") (pinfunction "1_1") (pintype "passive"))
      (node (ref "U2") (pin "7") (pinfunction "NRST_7") (pintype "bidirectional"))
    )
    (net (code "66") (name "/RTS") (class "Default")
      (node (ref "Q1") (pin "2") (pinfunction "E_2") (pintype "passive"))
      (node (ref "R6") (pin "1") (pinfunction "1_1") (pintype "passive"))
      (node (ref "U1") (pin "24") (pinfunction "RTS_24") (pintype "passive"))
    )
    (net (code "67") (name "/SWCLK") (class "Default")
      (node (ref "JP_SWD") (pin "3") (pinfunction "3_3") (pintype "passive"))
      (node (ref "U2") (pin "49") (pinfunction "PA14_49") (pintype "bidirectional"))
    )
    (net (code "68") (name "/SWDIO") (class "Default")
      (node (ref "JP_SWD") (pin "2") (pinfunction "2_2") (pintype "passive"))
      (node (ref "U2") (pin "46") (pinfunction "PA13_46") (pintype "bidirectional"))
    )
    (net (code "69") (name "/USART1_RX_DEBUG") (class "Default")
      (node (ref "U1") (pin "26") (pinfunction "TXD_26") (pintype "passive"))
      (node (ref "U2") (pin "43") (pinfunction "PA10_43") (pintype "bidirectional"))
    )
    (net (code "70") (name "/USART1_TX_DEBUG") (class "Default")
      (node (ref "U1") (pin "25") (pinfunction "RXD_25") (pintype "passive"))
      (node (ref "U2") (pin "42") (pinfunction "PA9_42") (pintype "bidirectional"))
    )
    (net (code "71") (name "/USART2_RX_PI") (class "Default")
      (node (ref "JP_PI") (pin "3") (pinfunction "3_3") (pintype "passive"))
      (node (ref "U2") (pin "17") (pinfunction "PA3_17") (pintype "bidirectional"))
    )
    (net (code "72") (name "/USART2_TX_PI") (class "Default")
      (node (ref "JP_PI") (pin "4") (pinfunction "4_4") (pintype "passive"))
      (node (ref "U2") (pin "16") (pinfunction "PA2_16") (pintype "bidirectional"))
    )
    (net (code "73") (name "/VIN_ADC") (class "Default")
      (node (ref "C12") (pin "2") (pinfunction "2_2") (pintype "passive"))
      (node (ref "R18") (pin "1") (pinfunction "1_1") (pintype "passive"))
      (node (ref "R19") (pin "2") (pinfunction "2_2") (pintype "passive"))
      (node (ref "U2") (pin "26") (pinfunction "PB0_26") (pintype "bidirectional"))
    )
    (net (code "74") (name "GND") (class "Default")
      (node (ref "AMS1") (pin "1") (pinfunction "GND_1") (pintype "passive"))
      (node (ref "C1") (pin "1") (pinfunction "1_1") (pintype "passive"))
      (node (ref "C10") (pin "2") (pinfunction "2_2") (pintype "passive"))
      (node (ref "C11") (pin "1") (pinfunction "1_1") (pintype "passive"))
      (node (ref "C12") (pin "1") (pinfunction "1_1") (pintype "passive"))
      (node (ref "C13") (pin "1") (pinfunction "1_1") (pintype "passive"))
      (node (ref "C14") (pin "1") (pinfunction "1_1") (pintype "passive"))
      (node (ref "C15") (pin "1") (pinfunction "1_1") (pintype "passive"))
      (node (ref "C16") (pin "1") (pinfunction "1_1") (pintype "passive"))
      (node (ref "C17") (pin "2") (pinfunction "2_2") (pintype "passive"))
      (node (ref "C18") (pin "1") (pinfunction "1_1") (pintype "passive"))
      (node (ref "C19") (pin "2") (pinfunction "2_2") (pintype "passive"))
      (node (ref "C2") (pin "1") (pinfunction "1_1") (pintype "passive"))
      (node (ref "C20") (pin "1") (pinfunction "1_1") (pintype "passive"))
      (node (ref "C21") (pin "1") (pinfunction "1_1") (pintype "passive"))
      (node (ref "C22") (pin "1") (pinfunction "1_1") (pintype "passive"))
      (node (ref "C23") (pin "1") (pinfunction "1_1") (pintype "passive"))
      (node (ref "C24") (pin "1") (pinfunction "1_1") (pintype "passive"))
      (node (ref "C25") (pin "1") (pinfunction "1_1") (pintype "passive"))
      (node (ref "C26") (pin "1") (pinfunction "1_1") (pintype "passive"))
      (node (ref "C3") (pin "1") (pinfunction "1_1") (pintype "passive"))
      (node (ref "C4") (pin "1") (pinfunction "1_1") (pintype "passive"))
      (node (ref "C5") (pin "1") (pinfunction "1_1") (pintype "passive"))
      (node (ref "C6") (pin "1") (pinfunction "1_1") (pintype "passive"))
      (node (ref "C7") (pin "2") (pinfunction "2_2") (pintype "passive"))
      (node (ref "C8") (pin "2") (pinfunction "2_2") (pintype "passive"))
      (node (ref "C9") (pin "2") (pinfunction "2_2") (pintype "passive"))
      (node (ref "D1") (pin "1") (pinfunction "A_1") (pintype "passive"))
      (node (ref "E1") (pin "2") (pinfunction "2_2") (pintype "passive"))
      (node (ref "E2") (pin "2") (pinfunction "2_2") (pintype "passive"))
      (node (ref "EM1") (pin "5") (pinfunction "5_5") (pintype "passive"))
      (node (ref "EM2") (pin "5") (pinfunction "5_5") (pintype "passive"))
      (node (ref "EM3") (pin "5") (pinfunction "5_5") (pintype "passive"))
      (node (ref "EM4") (pin "5") (pinfunction "5_5") (pintype "passive"))
      (node (ref "JP3") (pin "1") (pinfunction "1_1") (pintype "passive"))
      (node (ref "JP3") (pin "2") (pinfunction "2_2") (pintype "passive"))
      (node (ref "JP3") (pin "3") (pinfunction "3_3") (pintype "passive"))
      (node (ref "JP3") (pin "4") (pinfunction "4_4") (pintype "passive"))
      (node (ref "JP3") (pin "5") (pinfunction "5_5") (pintype "passive"))
      (node (ref "JP3") (pin "6") (pinfunction "6_6") (pintype "passive"))
      (node (ref "JP3") (pin "7") (pinfunction "7_7") (pintype "passive"))
      (node (ref "JP3") (pin "8") (pinfunction "8_8") (pintype "passive"))
      (node (ref "JP_PI") (pin "2") (pinfunction "2_2") (pintype "passive"))
      (node (ref "JP_SWD") (pin "4") (pinfunction "4_4") (pintype "passive"))
      (node (ref "K1") (pin "2") (pinfunction "2_2") (pintype "passive"))
      (node (ref "K1") (pin "4") (pinfunction "4_4") (pintype "passive"))
      (node (ref "K2") (pin "2") (pinfunction "2_2") (pintype "passive"))
      (node (ref "K2") (pin "4") (pinfunction "4_4") (pintype "passive"))
      (node (ref "K3") (pin "2") (pinfunction "2_2") (pintype "passive"))
      (node (ref "K3") (pin "4") (pinfunction "4_4") (pintype "passive"))
      (node (ref "LED_PW") (pin "2") (pinfunction "K_2") (pintype "passive"))
      (node (ref "LM1") (pin "3") (pinfunction "GND_3") (pintype "power_in"))
      (node (ref "LM1") (pin "5") (pinfunction "~{ON}/OFF_5") (pintype "input"))
      (node (ref "LM1") (pin "6") (pinfunction "GND_6") (pintype "power_in"))
      (node (ref "R11") (pin "1") (pinfunction "1_1") (pintype "passive"))
      (node (ref "R12") (pin "2") (pinfunction "2_2") (pintype "passive"))
      (node (ref "R19") (pin "1") (pinfunction "1_1") (pintype "passive"))
      (node (ref "R2") (pin "1") (pinfunction "1_1") (pintype "passive"))
      (node (ref "R3") (pin "1") (pinfunction "1_1") (pintype "passive"))
      (node (ref "R9") (pin "2") (pinfunction "2_2") (pintype "passive"))
      (node (ref "U1") (pin "29") (pinfunction "HEAT_TAB_29") (pintype "passive"))
      (node (ref "U1") (pin "3") (pinfunction "GND_3") (pintype "passive"))
      (node (ref "U2") (pin "12") (pinfunction "VSSA_12") (pintype "power_in"))
      (node (ref "U2") (pin "18") (pinfunction "VSS_4_18") (pintype "power_in"))
      (node (ref "U2") (pin "31") (pinfunction "VSS_1_31") (pintype "power_in"))
      (node (ref "U2") (pin "47") (pinfunction "VSS_2_47") (pintype "power_in"))
      (node (ref "U2") (pin "63") (pinfunction "VSS_3_63") (pintype "power_in"))
      (node (ref "U3") (pin "1") (pinfunction "CLKIN_1") (pintype "passive"))
      (node (ref "U3") (pin "11") (pinfunction "FSYNC_11") (pintype "passive"))
      (node (ref "U3") (pin "18") (pinfunction "GND_18") (pintype "passive"))
      (node (ref "U4") (pin "10") (pinfunction "PGND2_10") (pintype "passive"))
      (node (ref "U4") (pin "18") (pinfunction "GND_18") (pintype "passive"))
      (node (ref "U4") (pin "3") (pinfunction "PGND1_3") (pintype "passive"))
      (node (ref "U4") (pin "4") (pinfunction "PGND1_4") (pintype "passive"))
      (node (ref "U4") (pin "9") (pinfunction "PGND2_9") (pintype "passive"))
      (node (ref "U5") (pin "10") (pinfunction "PGND2_10") (pintype "passive"))
      (node (ref "U5") (pin "18") (pinfunction "GND_18") (pintype "passive"))
      (node (ref "U5") (pin "3") (pinfunction "PGND1_3") (pintype "passive"))
      (node (ref "U5") (pin "4") (pinfunction "PGND1_4") (pintype "passive"))
      (node (ref "U5") (pin "9") (pinfunction "PGND2_9") (pintype "passive"))
      (node (ref "USB1") (pin "1") (pinfunction "SH1_1") (pintype "passive"))
      (node (ref "USB1") (pin "2") (pinfunction "SH2_2") (pintype "passive"))
      (node (ref "USB1") (pin "3") (pinfunction "SH3_3") (pintype "passive"))
      (node (ref "USB1") (pin "4") (pinfunction "SH4_4") (pintype "passive"))
      (node (ref "USB1") (pin "A1") (pinfunction "GND_A1") (pintype "passive"))
      (node (ref "USB1") (pin "A12") (pinfunction "GND_A12") (pintype "passive"))
      (node (ref "USB1") (pin "B1") (pinfunction "GND_B1") (pintype "passive"))
      (node (ref "USB1") (pin "B12") (pinfunction "GND_B12") (pintype "passive"))
      (node (ref "VIN1") (pin "1") (pinfunction "1_1") (pintype "passive"))
      (node (ref "X1") (pin "2") (pinfunction "2_2") (pintype "passive"))
      (node (ref "X1") (pin "4") (pinfunction "4_4") (pintype "passive"))
    )
    (net (code "75") (name "Net-(D1-K)") (class "Default")
      (node (ref "D1") (pin "2") (pinfunction "K_2") (pintype "passive"))
      (node (ref "L1") (pin "1") (pinfunction "1_1") (pintype "passive"))
      (node (ref "LM1") (pin "2") (pinfunction "OUT_2") (pintype "power_in"))
    )
    (net (code "76") (name "Net-(D2-K)") (class "Default")
      (node (ref "D2") (pin "2") (pinfunction "K_2") (pintype "passive"))
      (node (ref "Q1") (pin "3") (pinfunction "C_3") (pintype "passive"))
      (node (ref "R4") (pin "2") (pinfunction "2_2") (pintype "passive"))
    )
    (net (code "77") (name "Net-(LED_BLUE-A)") (class "Default")
      (node (ref "LED_BLUE") (pin "1") (pinfunction "A_1") (pintype "passive"))
      (node (ref "R16") (pin "1") (pinfunction "1_1") (pintype "passive"))
    )
    (net (code "78") (name "Net-(LED_GREEN-A)") (class "Default")
      (node (ref "LED_GREEN") (pin "1") (pinfunction "A_1") (pintype "passive"))
      (node (ref "R15") (pin "1") (pinfunction "1_1") (pintype "passive"))
    )
    (net (code "79") (name "Net-(LED_PW-A)") (class "Default")
      (node (ref "LED_PW") (pin "1") (pinfunction "A_1") (pintype "passive"))
      (node (ref "R17") (pin "1") (pinfunction "1_1") (pintype "passive"))
    )
    (net (code "80") (name "Net-(Q1-B)") (class "Default")
      (node (ref "Q1") (pin "1") (pinfunction "B_1") (pintype "passive"))
      (node (ref "R5") (pin "2") (pinfunction "2_2") (pintype "passive"))
    )
    (net (code "81") (name "Net-(Q2-B)") (class "Default")
      (node (ref "Q2") (pin "1") (pinfunction "B_1") (pintype "passive"))
      (node (ref "R6") (pin "2") (pinfunction "2_2") (pintype "passive"))
    )
    (net (code "82") (name "Net-(Q2-C)") (class "Default")
      (node (ref "Q2") (pin "3") (pinfunction "C_3") (pintype "passive"))
      (node (ref "R7") (pin "1") (pinfunction "1_1") (pintype "passive"))
    )
    (net (code "83") (name "Net-(S1-Pad2)") (class "Default")
      (node (ref "S1") (pin "2") (pinfunction "2_2") (pintype "passive"))
      (node (ref "VIN1") (pin "2") (pinfunction "2_2") (pintype "passive"))
    )
    (net (code "84") (name "Net-(U1-*RST)") (class "Default")
      (node (ref "R1") (pin "1") (pinfunction "1_1") (pintype "passive"))
      (node (ref "U1") (pin "9") (pinfunction "*RST_9") (pintype "passive"))
    )
    (net (code "85") (name "Net-(U3-AD0)") (class "Default")
      (node (ref "R11") (pin "2") (pinfunction "2_2") (pintype "passive"))
      (node (ref "U3") (pin "9") (pinfunction "AD0_9") (pintype "passive"))
    )
    (net (code "86") (name "Net-(U3-CPOUT)") (class "Default")
      (node (ref "C7") (pin "1") (pinfunction "1_1") (pintype "passive"))
      (node (ref "U3") (pin "20") (pinfunction "CPOUT_20") (pintype "passive"))
    )
    (net (code "87") (name "Net-(U3-REGOUT)") (class "Default")
      (node (ref "C6") (pin "2") (pinfunction "2_2") (pintype "passive"))
      (node (ref "U3") (pin "10") (pinfunction "REGOUT_10") (pintype "passive"))
    )
    (net (code "88") (name "Net-(USB1-CC1)") (class "Default")
      (node (ref "R2") (pin "2") (pinfunction "2_2") (pintype "passive"))
      (node (ref "USB1") (pin "A5") (pinfunction "CC1_A5") (pintype "passive"))
    )
    (net (code "89") (name "Net-(USB1-CC2)") (class "Default")
      (node (ref "R3") (pin "2") (pinfunction "2_2") (pintype "passive"))
      (node (ref "USB1") (pin "B5") (pinfunction "CC2_B5") (pintype "passive"))
    )
    (net (code "90") (name "USB_5V") (class "Default")
      (node (ref "F1") (pin "1") (pinfunction "1_1") (pintype "passive"))
      (node (ref "R1") (pin "2") (pinfunction "2_2") (pintype "passive"))
      (node (ref "U1") (pin "7") (pinfunction "REGIN_7") (pintype "passive"))
      (node (ref "U1") (pin "8") (pinfunction "VBUS_8") (pintype "passive"))
      (node (ref "USB1") (pin "A4") (pinfunction "VBUS_A4") (pintype "passive"))
      (node (ref "USB1") (pin "A9") (pinfunction "VBUS_A9") (pintype "passive"))
      (node (ref "USB1") (pin "B4") (pinfunction "VBUS_B4") (pintype "passive"))
      (node (ref "USB1") (pin "B9") (pinfunction "VBUS_B9") (pintype "passive"))
    )
    (net (code "91") (name "VCC3V3") (class "Default")
      (node (ref "AMS1") (pin "2") (pinfunction "Vout_2") (pintype "passive"))
      (node (ref "AMS1") (pin "4") (pinfunction "Vout_4") (pintype "passive"))
      (node (ref "C21") (pin "2") (pinfunction "2_2") (pintype "passive"))
      (node (ref "C22") (pin "2") (pinfunction "2_2") (pintype "passive"))
      (node (ref "C23") (pin "2") (pinfunction "2_2") (pintype "passive"))
      (node (ref "C24") (pin "2") (pinfunction "2_2") (pintype "passive"))
      (node (ref "C25") (pin "2") (pinfunction "2_2") (pintype "passive"))
      (node (ref "C26") (pin "2") (pinfunction "2_2") (pintype "passive"))
      (node (ref "C3") (pin "2") (pinfunction "2_2") (pintype "passive"))
      (node (ref "C4") (pin "2") (pinfunction "2_2") (pintype "passive"))
      (node (ref "C5") (pin "2") (pinfunction "2_2") (pintype "passive"))
      (node (ref "C8") (pin "1") (pinfunction "1_1") (pintype "passive"))
      (node (ref "JP2") (pin "1") (pinfunction "1_1") (pintype "passive"))
      (node (ref "JP2") (pin "2") (pinfunction "2_2") (pintype "passive"))
      (node (ref "JP2") (pin "3") (pinfunction "3_3") (pintype "passive"))
      (node (ref "JP2") (pin "4") (pinfunction "4_4") (pintype "passive"))
      (node (ref "JP2") (pin "5") (pinfunction "5_5") (pintype "passive"))
      (node (ref "JP2") (pin "6") (pinfunction "6_6") (pintype "passive"))
      (node (ref "JP2") (pin "7") (pinfunction "7_7") (pintype "passive"))
      (node (ref "JP2") (pin "8") (pinfunction "8_8") (pintype "passive"))
      (node (ref "JP_SWD") (pin "1") (pinfunction "1_1") (pintype "passive"))
      (node (ref "Q2") (pin "2") (pinfunction "E_2") (pintype "passive"))
      (node (ref "R10") (pin "2") (pinfunction "2_2") (pintype "passive"))
      (node (ref "R14") (pin "2") (pinfunction "2_2") (pintype "passive"))
      (node (ref "R15") (pin "2") (pinfunction "2_2") (pintype "passive"))
      (node (ref "R16") (pin "2") (pinfunction "2_2") (pintype "passive"))
      (node (ref "R17") (pin "2") (pinfunction "2_2") (pintype "passive"))
      (node (ref "R4") (pin "1") (pinfunction "1_1") (pintype "passive"))
      (node (ref "R8") (pin "2") (pinfunction "2_2") (pintype "passive"))
      (node (ref "U2") (pin "1") (pinfunction "VBAT_1") (pintype "power_in"))
      (node (ref "U2") (pin "13") (pinfunction "VDDA_13") (pintype "power_in"))
      (node (ref "U2") (pin "19") (pinfunction "VDD_4_19") (pintype "power_in"))
      (node (ref "U2") (pin "32") (pinfunction "VDD_1_32") (pintype "power_in"))
      (node (ref "U2") (pin "48") (pinfunction "VDD_2_48") (pintype "power_in"))
      (node (ref "U2") (pin "64") (pinfunction "VDD_3_64") (pintype "power_in"))
      (node (ref "U3") (pin "13") (pinfunction "VDD_13") (pintype "passive"))
      (node (ref "U3") (pin "8") (pinfunction "VLogic_8") (pintype "passive"))
    )
    (net (code "92") (name "VCC5V") (class "Default")
      (node (ref "AMS1") (pin "3") (pinfunction "Vin_3") (pintype "passive"))
      (node (ref "C1") (pin "2") (pinfunction "2_2") (pintype "passive"))
      (node (ref "C17") (pin "1") (pinfunction "1_1") (pintype "passive"))
      (node (ref "C18") (pin "2") (pinfunction "2_2") (pintype "passive"))
      (node (ref "C19") (pin "1") (pinfunction "1_1") (pintype "passive"))
      (node (ref "C2") (pin "2") (pinfunction "2_2") (pintype "passive"))
      (node (ref "C20") (pin "2") (pinfunction "2_2") (pintype "passive"))
      (node (ref "E1") (pin "1") (pinfunction "1_1") (pintype "passive"))
      (node (ref "EM1") (pin "2") (pinfunction "2_2") (pintype "passive"))
      (node (ref "EM2") (pin "2") (pinfunction "2_2") (pintype "passive"))
      (node (ref "EM3") (pin "2") (pinfunction "2_2") (pintype "passive"))
      (node (ref "EM4") (pin "2") (pinfunction "2_2") (pintype "passive"))
      (node (ref "F1") (pin "2") (pinfunction "2_2") (pintype "passive"))
      (node (ref "JP1") (pin "1") (pinfunction "1_1") (pintype "passive"))
      (node (ref "JP1") (pin "2") (pinfunction "2_2") (pintype "passive"))
      (node (ref "JP1") (pin "3") (pinfunction "3_3") (pintype "passive"))
      (node (ref "JP1") (pin "4") (pinfunction "4_4") (pintype "passive"))
      (node (ref "JP1") (pin "5") (pinfunction "5_5") (pintype "passive"))
      (node (ref "JP1") (pin "6") (pinfunction "6_6") (pintype "passive"))
      (node (ref "JP1") (pin "7") (pinfunction "7_7") (pintype "passive"))
      (node (ref "JP1") (pin "8") (pinfunction "8_8") (pintype "passive"))
      (node (ref "JP_PI") (pin "1") (pinfunction "1_1") (pintype "passive"))
      (node (ref "L1") (pin "2") (pinfunction "2_2") (pintype "passive"))
      (node (ref "LM1") (pin "4") (pinfunction "FB_4") (pintype "input"))
      (node (ref "RP12") (pin "5") (pinfunction "5_5") (pintype "passive"))
      (node (ref "RP12") (pin "6") (pinfunction "6_6") (pintype "passive"))
      (node (ref "RP12") (pin "7") (pinfunction "7_7") (pintype "passive"))
      (node (ref "RP12") (pin "8") (pinfunction "8_8") (pintype "passive"))
      (node (ref "RP34") (pin "5") (pinfunction "5_5") (pintype "passive"))
      (node (ref "RP34") (pin "6") (pinfunction "6_6") (pintype "passive"))
      (node (ref "RP34") (pin "7") (pinfunction "7_7") (pintype "passive"))
      (node (ref "RP34") (pin "8") (pinfunction "8_8") (pintype "passive"))
      (node (ref "U4") (pin "19") (pinfunction "STBY_19") (pintype "passive"))
      (node (ref "U4") (pin "20") (pinfunction "VCC_20") (pintype "passive"))
      (node (ref "U5") (pin "19") (pinfunction "STBY_19") (pintype "passive"))
      (node (ref "U5") (pin "20") (pinfunction "VCC_20") (pintype "passive"))
    )
    (net (code "93") (name "VCC12V") (class "Default")
      (node (ref "C13") (pin "2") (pinfunction "2_2") (pintype "passive"))
      (node (ref "C14") (pin "2") (pinfunction "2_2") (pintype "passive"))
      (node (ref "C15") (pin "2") (pinfunction "2_2") (pintype "passive"))
      (node (ref "C16") (pin "2") (pinfunction "2_2") (pintype "passive"))
      (node (ref "E2") (pin "1") (pinfunction "1_1") (pintype "passive"))
      (node (ref "LM1") (pin "1") (pinfunction "IN_1") (pintype "power_in"))
      (node (ref "R18") (pin "2") (pinfunction "2_2") (pintype "passive"))
      (node (ref "S1") (pin "3") (pinfunction "3_3") (pintype "passive"))
      (node (ref "U4") (pin "13") (pinfunction "VM2_13") (pintype "passive"))
      (node (ref "U4") (pin "14") (pinfunction "VM3_14") (pintype "passive"))
      (node (ref "U4") (pin "24") (pinfunction "VM1_24") (pintype "passive"))
      (node (ref "U5") (pin "13") (pinfunction "VM2_13") (pintype "passive"))
      (node (ref "U5") (pin "14") (pinfunction "VM3_14") (pintype "passive"))
      (node (ref "U5") (pin "24") (pinfunction "VM1_24") (pintype "passive"))
    )
    (net (code "94") (name "unconnected-(S1-Pad1)") (class "Default")
      (node (ref "S1") (pin "1") (pinfunction "1_1") (pintype "passive"))
    )
    (net (code "95") (name "unconnected-(U1-*SUSPEND-Pad11)") (class "Default")
      (node (ref "U1") (pin "11") (pinfunction "*SUSPEND_11") (pintype "passive"))
    )
    (net (code "96") (name "unconnected-(U1-CTS-Pad23)") (class "Default")
      (node (ref "U1") (pin "23") (pinfunction "CTS_23") (pintype "passive"))
    )
    (net (code "97") (name "unconnected-(U1-DCD-Pad1)") (class "Default")
      (node (ref "U1") (pin "1") (pinfunction "DCD_1") (pintype "passive"))
    )
    (net (code "98") (name "unconnected-(U1-DSR-Pad27)") (class "Default")
      (node (ref "U1") (pin "27") (pinfunction "DSR_27") (pintype "passive"))
    )
    (net (code "99") (name "unconnected-(U1-NC-Pad10)") (class "Default")
      (node (ref "U1") (pin "10") (pinfunction "NC_10") (pintype "passive"))
    )
    (net (code "100") (name "unconnected-(U1-NC-Pad13)") (class "Default")
      (node (ref "U1") (pin "13") (pinfunction "NC_13") (pintype "passive"))
    )
    (net (code "101") (name "unconnected-(U1-NC-Pad14)") (class "Default")
      (node (ref "U1") (pin "14") (pinfunction "NC_14") (pintype "passive"))
    )
    (net (code "102") (name "unconnected-(U1-NC-Pad15)") (class "Default")
      (node (ref "U1") (pin "15") (pinfunction "NC_15") (pintype "passive"))
    )
    (net (code "103") (name "unconnected-(U1-NC-Pad16)") (class "Default")
      (node (ref "U1") (pin "16") (pinfunction "NC_16") (pintype "passive"))
    )
    (net (code "104") (name "unconnected-(U1-NC-Pad17)") (class "Default")
      (node (ref "U1") (pin "17") (pinfunction "NC_17") (pintype "passive"))
    )
    (net (code "105") (name "unconnected-(U1-NC-Pad18)") (class "Default")
      (node (ref "U1") (pin "18") (pinfunction "NC_18") (pintype "passive"))
    )
    (net (code "106") (name "unconnected-(U1-NC-Pad19)") (class "Default")
      (node (ref "U1") (pin "19") (pinfunction "NC_19") (pintype "passive"))
    )
    (net (code "107") (name "unconnected-(U1-NC-Pad20)") (class "Default")
      (node (ref "U1") (pin "20") (pinfunction "NC_20") (pintype "passive"))
    )
    (net (code "108") (name "unconnected-(U1-NC-Pad21)") (class "Default")
      (node (ref "U1") (pin "21") (pinfunction "NC_21") (pintype "passive"))
    )
    (net (code "109") (name "unconnected-(U1-NC-Pad22)") (class "Default")
      (node (ref "U1") (pin "22") (pinfunction "NC_22") (pintype "passive"))
    )
    (net (code "110") (name "unconnected-(U1-RI-Pad2)") (class "Default")
      (node (ref "U1") (pin "2") (pinfunction "RI_2") (pintype "passive"))
    )
    (net (code "111") (name "unconnected-(U1-SUSPEND-Pad12)") (class "Default")
      (node (ref "U1") (pin "12") (pinfunction "SUSPEND_12") (pintype "passive"))
    )
    (net (code "112") (name "unconnected-(U1-VDD-Pad6)") (class "Default")
      (node (ref "U1") (pin "6") (pinfunction "VDD_6") (pintype "passive"))
    )
    (net (code "113") (name "unconnected-(U3-A_CL-Pad7)") (class "Default")
      (node (ref "U3") (pin "7") (pinfunction "A_CL_7") (pintype "passive+no_connect"))
    )
    (net (code "114") (name "unconnected-(U3-A_DA-Pad6)") (class "Default")
      (node (ref "U3") (pin "6") (pinfunction "A_DA_6") (pintype "passive+no_connect"))
    )
    (net (code "115") (name "unconnected-(U3-CLKOUT-Pad22)") (class "Default")
      (node (ref "U3") (pin "22") (pinfunction "CLKOUT_22") (pintype "passive+no_connect"))
    )
    (net (code "116") (name "unconnected-(U3-NC-Pad2)") (class "Default")
      (node (ref "U3") (pin "2") (pinfunction "NC_2") (pintype "passive+no_connect"))
    )
    (net (code "117") (name "unconnected-(U3-NC-Pad3)") (class "Default")
      (node (ref "U3") (pin "3") (pinfunction "NC_3") (pintype "passive+no_connect"))
    )
    (net (code "118") (name "unconnected-(U3-NC-Pad4)") (class "Default")
      (node (ref "U3") (pin "4") (pinfunction "NC_4") (pintype "passive+no_connect"))
    )
    (net (code "119") (name "unconnected-(U3-NC-Pad5)") (class "Default")
      (node (ref "U3") (pin "5") (pinfunction "NC_5") (pintype "passive+no_connect"))
    )
    (net (code "120") (name "unconnected-(U3-NC-Pad14)") (class "Default")
      (node (ref "U3") (pin "14") (pinfunction "NC_14") (pintype "passive"))
    )
    (net (code "121") (name "unconnected-(U3-NC-Pad15)") (class "Default")
      (node (ref "U3") (pin "15") (pinfunction "NC_15") (pintype "passive"))
    )
    (net (code "122") (name "unconnected-(U3-NC-Pad16)") (class "Default")
      (node (ref "U3") (pin "16") (pinfunction "NC_16") (pintype "passive"))
    )
    (net (code "123") (name "unconnected-(U3-NC-Pad17)") (class "Default")
      (node (ref "U3") (pin "17") (pinfunction "NC_17") (pintype "passive"))
    )
    (net (code "124") (name "unconnected-(U3-RESV-Pad19)") (class "Default")
      (node (ref "U3") (pin "19") (pinfunction "RESV_19") (pintype "passive+no_connect"))
    )
    (net (code "125") (name "unconnected-(U3-RESV-Pad21)") (class "Default")
      (node (ref "U3") (pin "21") (pinfunction "RESV_21") (pintype "passive+no_connect"))
    )
    (net (code "126") (name "unconnected-(USB1-RX1+-PadB11)") (class "Default")
      (node (ref "USB1") (pin "B11") (pinfunction "RX1+_B11") (pintype "passive"))
    )
    (net (code "127") (name "unconnected-(USB1-RX1--PadB10)") (class "Default")
      (node (ref "USB1") (pin "B10") (pinfunction "RX1-_B10") (pintype "passive"))
    )
    (net (code "128") (name "unconnected-(USB1-RX2+-PadA11)") (class "Default")
      (node (ref "USB1") (pin "A11") (pinfunction "RX2+_A11") (pintype "passive"))
    )
    (net (code "129") (name "unconnected-(USB1-RX2--PadA10)") (class "Default")
      (node (ref "USB1") (pin "A10") (pinfunction "RX2-_A10") (pintype "passive"))
    )
    (net (code "130") (name "unconnected-(USB1-SBU1-PadA8)") (class "Default")
      (node (ref "USB1") (pin "A8") (pinfunction "SBU1_A8") (pintype "passive"))
    )
    (net (code "131") (name "unconnected-(USB1-SBU2-PadB8)") (class "Default")
      (node (ref "USB1") (pin "B8") (pinfunction "SBU2_B8") (pintype "passive"))
    )
    (net (code "132") (name "unconnected-(USB1-TX1+-PadA2)") (class "Default")
      (node (ref "USB1") (pin "A2") (pinfunction "TX1+_A2") (pintype "passive"))
    )
    (net (code "133") (name "unconnected-(USB1-TX1--PadA3)") (class "Default")
      (node (ref "USB1") (pin "A3") (pinfunction "TX1-_A3") (pintype "passive"))
    )
    (net (code "134") (name "unconnected-(USB1-TX2+-PadB2)") (class "Default")
      (node (ref "USB1") (pin "B2") (pinfunction "TX2+_B2") (pintype "passive"))
    )
    (net (code "135") (name "unconnected-(USB1-TX2--PadB3)") (class "Default")
      (node (ref "USB1") (pin "B3") (pinfunction "TX2-_B3") (pintype "passive"))
    )
  )
)
